# Voltage_Regulators.net
KiCad netlist of a schematic drawn in Altium Designer
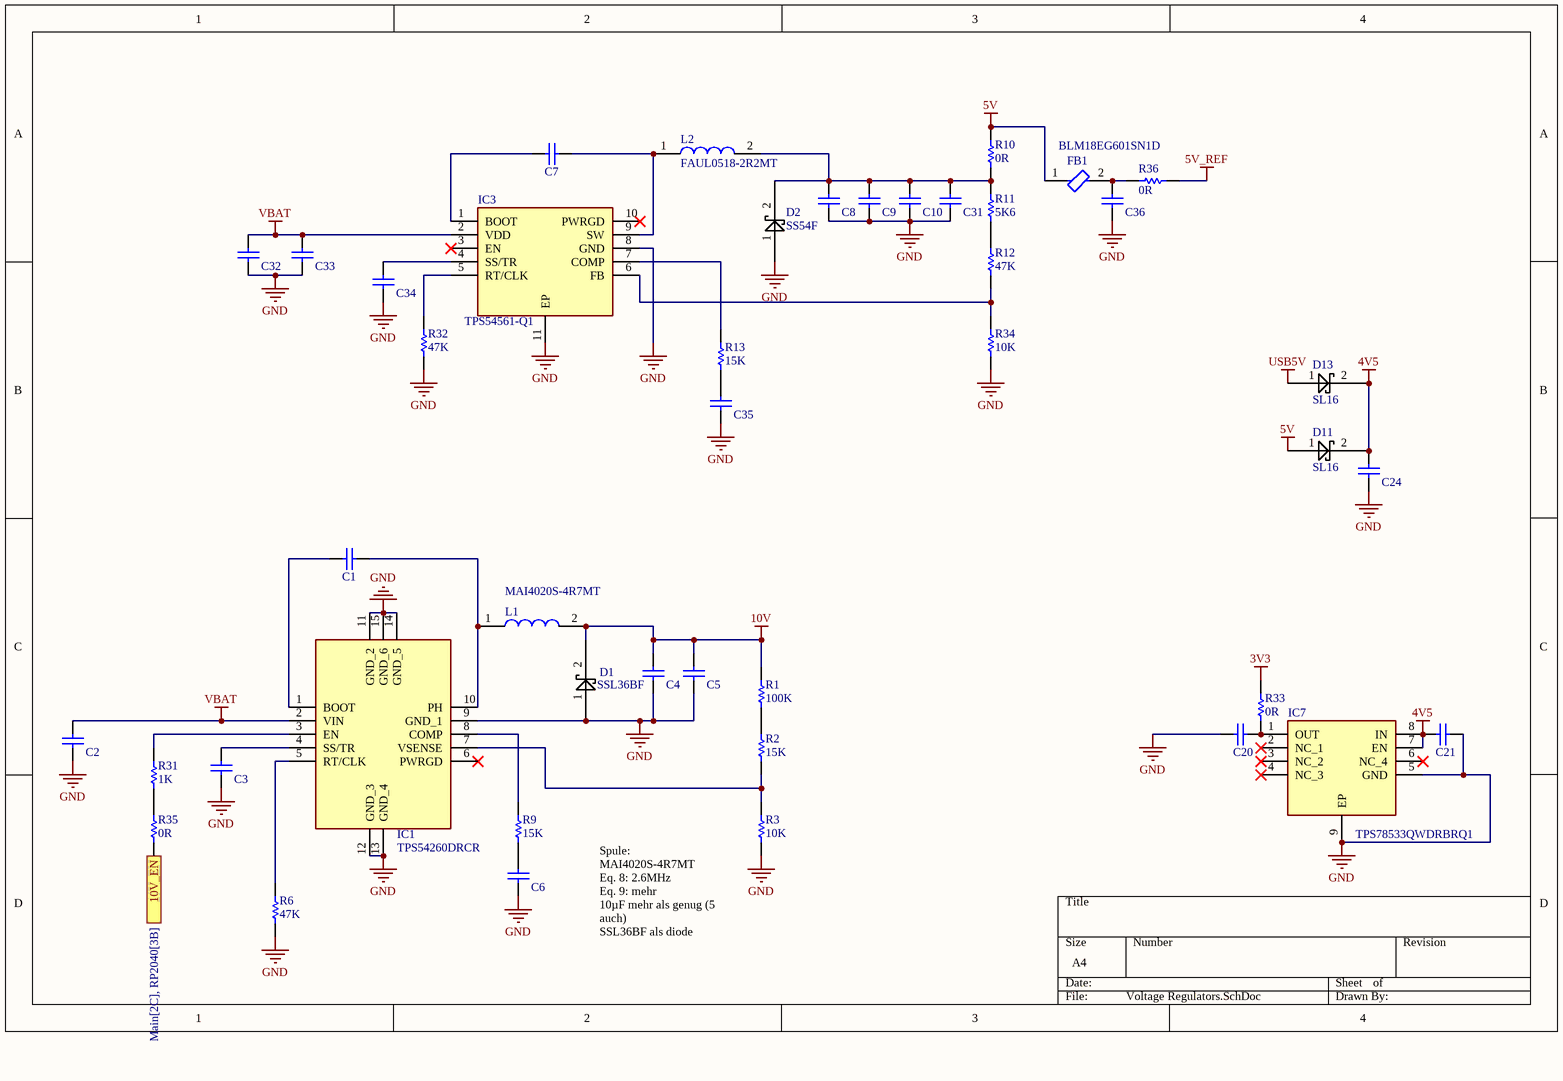
[diagram p0: Voltage Regulators.SchDoc]

(export (version "E")
  (design (tool "Eeschema 10.0.6"))
  (components
    (comp (ref "C1")
      (value "100nF")
      (footprint "WCAP-CSGP_0603_L1.6W0.8H0.8_Reflow")
      (description "WCAP-CSGP Multilayer Ceramic Chip Capacitor, General Purpose, size 0603, X7R, 100nF, 16VDC")
      (fields
        (field (name "MANUFACTURER PART NUMBER") "885012206046")
        (field (name "MANUFACTURER") "Wurth Elektronik")
      )
      (libsource (lib "Altium_WCAP-CSGP (rev22e)") (part "885012206046"))
    )
    (comp (ref "C2")
      (value "3.3µF")
      (footprint "WCAP-CSGP_1206_L3.2W1.6H1.6")
      (description "TDK C3216X7S2A335KT000N\r\n3.3µF MLCC 1206 100V X7S")
      (fields
        (field (name "MANUFACTURER PART NUMBER") "885012208124")
        (field (name "MANUFACTURER") "Wurth Elektronik")
      )
      (libsource (lib "Altium_WCAP-CSGP (rev22e)") (part "885012208124"))
    )
    (comp (ref "C3")
      (value "10nF")
      (footprint "WCAP-CSGP_0603_L1.6W0.8H0.8_Reflow")
      (description "WCAP-CSGP Multilayer Ceramic Chip Capacitor, General Purpose, size 0603, X7R, 10nF, 16VDC")
      (fields
        (field (name "MANUFACTURER PART NUMBER") "885012206040")
        (field (name "MANUFACTURER") "Wurth Elektronik")
      )
      (libsource (lib "Altium_WCAP-CSGP (rev22e)") (part "885012206040"))
    )
    (comp (ref "C4")
      (value "4.7µF")
      (footprint "WCAP-CSGP_0805_L2W1.25H1.25")
      (description "CL21A475KAQNNNG")
      (fields
        (field (name "MANUFACTURER PART NUMBER") "885012107013")
        (field (name "MANUFACTURER") "Wurth Elektronik")
      )
      (libsource (lib "Altium_WCAP-CSGP (rev22e)") (part "885012107013"))
    )
    (comp (ref "C5")
      (value "4.7µF")
      (footprint "WCAP-CSGP_0805_L2W1.25H1.25")
      (description "CL21A475KAQNNNG")
      (fields
        (field (name "MANUFACTURER PART NUMBER") "885012107013")
        (field (name "MANUFACTURER") "Wurth Elektronik")
      )
      (libsource (lib "Altium_WCAP-CSGP (rev22e)") (part "885012107013"))
    )
    (comp (ref "C6")
      (value "2.5pF")
      (footprint "WCAP-CSGP_0603_L1.6W0.8H0.8_Reflow")
      (description "TCC0603COG2R5C500CT")
      (fields
        (field (name "MANUFACTURER PART NUMBER") "885012006030")
        (field (name "MANUFACTURER") "Wurth Elektronik")
      )
      (libsource (lib "Altium_WCAP-CSGP (rev22e)") (part "885012006030"))
    )
    (comp (ref "C7")
      (value "100nF")
      (footprint "WCAP-CSGP_0603_L1.6W0.8H0.8_Reflow")
      (description "WCAP-CSGP Multilayer Ceramic Chip Capacitor, General Purpose, size 0603, X7R, 100nF, 16VDC")
      (fields
        (field (name "MANUFACTURER PART NUMBER") "885012206046")
        (field (name "MANUFACTURER") "Wurth Elektronik")
      )
      (libsource (lib "Altium_WCAP-CSGP (rev22e)") (part "885012206046"))
    )
    (comp (ref "C8")
      (value "4.7µF")
      (footprint "WCAP-CSGP_0805_L2W1.25H1.25")
      (description "CL21A475KAQNNNG")
      (fields
        (field (name "MANUFACTURER PART NUMBER") "885012107013")
        (field (name "MANUFACTURER") "Wurth Elektronik")
      )
      (libsource (lib "Altium_WCAP-CSGP (rev22e)") (part "885012107013"))
    )
    (comp (ref "C9")
      (value "4.7µF")
      (footprint "WCAP-CSGP_0805_L2W1.25H1.25")
      (description "CL21A475KAQNNNG")
      (fields
        (field (name "MANUFACTURER PART NUMBER") "885012107013")
        (field (name "MANUFACTURER") "Wurth Elektronik")
      )
      (libsource (lib "Altium_WCAP-CSGP (rev22e)") (part "885012107013"))
    )
    (comp (ref "C10")
      (value "4.7µF")
      (footprint "WCAP-CSGP_0805_L2W1.25H1.25")
      (description "CL21A475KAQNNNG")
      (fields
        (field (name "MANUFACTURER PART NUMBER") "885012107013")
        (field (name "MANUFACTURER") "Wurth Elektronik")
      )
      (libsource (lib "Altium_WCAP-CSGP (rev22e)") (part "885012107013"))
    )
    (comp (ref "C20")
      (value "1µF")
      (footprint "WCAP-CSGP_0603_L1.6W0.8H0.8_Reflow")
      (description "WCAP-CSGP Multilayer Ceramic Chip Capacitor, General Purpose, size 0603, X7R, 1µF, 10VDC")
      (fields
        (field (name "MANUFACTURER PART NUMBER") "885012206026")
        (field (name "MANUFACTURER") "Wurth Elektronik")
      )
      (libsource (lib "Altium_WCAP-CSGP (rev22e)") (part "885012206026"))
    )
    (comp (ref "C21")
      (value "1µF")
      (footprint "WCAP-CSGP_0603_L1.6W0.8H0.8_Reflow")
      (description "WCAP-CSGP Multilayer Ceramic Chip Capacitor, General Purpose, size 0603, X7R, 1µF, 10VDC")
      (fields
        (field (name "MANUFACTURER PART NUMBER") "885012206026")
        (field (name "MANUFACTURER") "Wurth Elektronik")
      )
      (libsource (lib "Altium_WCAP-CSGP (rev22e)") (part "885012206026"))
    )
    (comp (ref "C24")
      (value "1µF")
      (footprint "WCAP-CSGP_0603_L1.6W0.8H0.8_Reflow")
      (description "WCAP-CSGP Multilayer Ceramic Chip Capacitor, General Purpose, size 0603, X5R, 1µF, 16VDC")
      (fields
        (field (name "MANUFACTURER PART NUMBER") "885012106017")
        (field (name "MANUFACTURER") "Wurth Elektronik")
      )
      (libsource (lib "Altium_WCAP-CSGP (rev22e)") (part "885012106017"))
    )
    (comp (ref "C31")
      (value "4.7µF")
      (footprint "WCAP-CSGP_0805_L2W1.25H1.25")
      (description "CL21A475KAQNNNG")
      (fields
        (field (name "MANUFACTURER PART NUMBER") "885012107013")
        (field (name "MANUFACTURER") "Wurth Elektronik")
      )
      (libsource (lib "Altium_WCAP-CSGP (rev22e)") (part "885012107013"))
    )
    (comp (ref "C32")
      (value "2.2µF")
      (footprint "WCAP-CSGP_0805_L2W1.25H1.25")
      (description "CL21B225KBYNNNE")
      (fields
        (field (name "MANUFACTURER PART NUMBER") "885012107013")
        (field (name "MANUFACTURER") "Wurth Elektronik")
      )
      (libsource (lib "Altium_WCAP-CSGP (rev22e)") (part "885012107013"))
    )
    (comp (ref "C33")
      (value "2.2µF")
      (footprint "WCAP-CSGP_0805_L2W1.25H1.25")
      (description "CL21B225KBYNNNE")
      (fields
        (field (name "MANUFACTURER PART NUMBER") "885012107013")
        (field (name "MANUFACTURER") "Wurth Elektronik")
      )
      (libsource (lib "Altium_WCAP-CSGP (rev22e)") (part "885012107013"))
    )
    (comp (ref "C34")
      (value "10nF")
      (footprint "WCAP-CSGP_0603_L1.6W0.8H0.8_Reflow")
      (description "WCAP-CSGP Multilayer Ceramic Chip Capacitor, General Purpose, size 0603, X7R, 10nF, 16VDC")
      (fields
        (field (name "MANUFACTURER PART NUMBER") "885012206040")
        (field (name "MANUFACTURER") "Wurth Elektronik")
      )
      (libsource (lib "Altium_WCAP-CSGP (rev22e)") (part "885012206040"))
    )
    (comp (ref "C35")
      (value "1nF")
      (footprint "WCAP-CSGP_0603_L1.6W0.8H0.8_Reflow")
      (description "TCC0603COG2R5C500CT")
      (fields
        (field (name "MANUFACTURER PART NUMBER") "885012006030")
        (field (name "MANUFACTURER") "Wurth Elektronik")
      )
      (libsource (lib "Altium_WCAP-CSGP (rev22e)") (part "885012006030"))
    )
    (comp (ref "C36")
      (value "1µF")
      (footprint "WCAP-CSGP_0603_L1.6W0.8H0.8_Reflow")
      (description "WCAP-CSGP Multilayer Ceramic Chip Capacitor, General Purpose, size 0603, X7R, 1µF, 10VDC")
      (fields
        (field (name "MANUFACTURER PART NUMBER") "885012206026")
        (field (name "MANUFACTURER") "Wurth Elektronik")
      )
      (libsource (lib "Altium_WCAP-CSGP (rev22e)") (part "885012206026"))
    )
    (comp (ref "D1")
      (value "SSL36BF")
      (footprint "SSL36BF")
      (libsource (lib "Custom Components") (part "SSL36BF"))
    )
    (comp (ref "D2") (value "SS54F") (footprint "SS54F") (libsource (lib "Custom Components") (part "SS54F")))
    (comp (ref "D11") (value "SL16") (footprint "SL16") (libsource (lib "Custom Components") (part "SL16")))
    (comp (ref "D13") (value "SL16") (footprint "SL16") (libsource (lib "Custom Components") (part "SL16")))
    (comp (ref "FB1")
      (value "BLM18EG601SN1D")
      (footprint "FP-BLM18-0_15-t0_8-MFG")
      (description "Chip Ferrite Bead, 0603, 600Ω @ 100MHz, 0.35Ω, 25%, 500mA")
      (fields (field (name "TOLERANCE") "25%"))
      (libsource (lib "Altium Content Vault") (part "5f30dd21d616792df468990f7003faa"))
    )
    (comp (ref "IC1")
      (value "TPS54260DRCR")
      (footprint "Custom Components:TPS54040ADRCT")
      (description "Integrated Circuit")
      (fields (field (name "MOUSER PART NUMBER") "595-TPS54260DRCR"))
      (libsource (lib "*") (part "TPS54260DRCR"))
    )
    (comp (ref "IC3")
      (value "TPS54561-Q1")
      (footprint "Custom Components:SON80P400X400X80-11N")
      (description "Integrated Circuit")
      (libsource (lib "*") (part "TPS54561-Q1"))
    )
    (comp (ref "IC7")
      (value "TPS78533QWDRBRQ1")
      (footprint "Custom Components:SON65P300X300X100-9N-D")
      (description "Integrated Circuit")
      (fields (field (name "MOUSER PART NUMBER") "595-TPS78533QWDRBRQ1"))
      (libsource (lib "*") (part "TPS78533QWDRBRQ1"))
    )
    (comp (ref "L1")
      (value "MAI4020S-4R7MT")
      (footprint "MAI4020S-4R7MT")
      (libsource (lib "Custom Components") (part "MAI4020S-4R7MT"))
    )
    (comp (ref "L2")
      (value "FAUL0518-2R2MT")
      (footprint "FAUL0518-2R2MT")
      (libsource (lib "Custom Components") (part "FAUL0518-2R2MT"))
    )
    (comp (ref "R1")
      (value "100K")
      (footprint "RESC0603(1608)_N")
      (description "Chipwiderstand, SMD, Baureihe MC, 1%")
      (fields (field (name "MANUFACTURER") "Multicomp"))
      (libsource (lib "Standardbauteile") (part "Res 100K"))
    )
    (comp (ref "R2")
      (value "15K")
      (footprint "RESC0603(1608)_N")
      (description "Chipwiderstand, SMD, Baureihe MC, 1%")
      (fields (field (name "MANUFACTURER") "Multicomp"))
      (libsource (lib "Standardbauteile") (part "Res 12K"))
    )
    (comp (ref "R3")
      (value "10K")
      (footprint "RESC0603(1608)_N")
      (description "Chipwiderstand, SMD, Baureihe MC, 1%")
      (fields (field (name "MANUFACTURER") "Multicomp"))
      (libsource (lib "Standardbauteile") (part "Res 10K"))
    )
    (comp (ref "R6")
      (value "47K")
      (footprint "RESC0603(1608)_N")
      (description "Chipwiderstand, SMD, Baureihe MC, 1%")
      (fields (field (name "MANUFACTURER") "Multicomp"))
      (libsource (lib "Standardbauteile") (part "Res 47R"))
    )
    (comp (ref "R9")
      (value "15K")
      (footprint "RESC0603(1608)_N")
      (description "Chipwiderstand, SMD, Baureihe MC, 1%")
      (fields (field (name "MANUFACTURER") "Multicomp"))
      (libsource (lib "Standardbauteile") (part "Res 12K"))
    )
    (comp (ref "R10")
      (value "0R")
      (footprint "RESC0603(1608)_N")
      (description "Chipwiderstand, SMD, Baureihe MC, 1%")
      (fields (field (name "MANUFACTURER") "Multicomp"))
      (libsource (lib "Standardbauteile") (part "Res 0R"))
    )
    (comp (ref "R11")
      (value "5K6")
      (footprint "RESC0603(1608)_N")
      (description "Chipwiderstand, SMD, Baureihe MC, 1%")
      (fields (field (name "MANUFACTURER") "Multicomp"))
      (libsource (lib "Standardbauteile") (part "Res 100K"))
    )
    (comp (ref "R12")
      (value "47K")
      (footprint "RESC0603(1608)_N")
      (description "Chipwiderstand, SMD, Baureihe MC, 1%")
      (fields (field (name "MANUFACTURER") "Multicomp"))
      (libsource (lib "Standardbauteile") (part "Res 12K"))
    )
    (comp (ref "R13")
      (value "15K")
      (footprint "RESC0603(1608)_N")
      (description "Chipwiderstand, SMD, Baureihe MC, 1%")
      (fields (field (name "MANUFACTURER") "Multicomp"))
      (libsource (lib "Standardbauteile") (part "Res 12K"))
    )
    (comp (ref "R31")
      (value "1K")
      (footprint "RESC0603(1608)_N")
      (description "Chipwiderstand, SMD, Baureihe MC, 1%")
      (fields (field (name "MANUFACTURER") "Multicomp"))
      (libsource (lib "Standardbauteile") (part "Res 1K"))
    )
    (comp (ref "R32")
      (value "47K")
      (footprint "RESC0603(1608)_N")
      (description "Chipwiderstand, SMD, Baureihe MC, 1%")
      (fields (field (name "MANUFACTURER") "Multicomp"))
      (libsource (lib "Standardbauteile") (part "Res 47R"))
    )
    (comp (ref "R33")
      (value "0R")
      (footprint "RESC0603(1608)_N")
      (description "Chipwiderstand, SMD, Baureihe MC, 1%")
      (fields (field (name "MANUFACTURER") "Multicomp"))
      (libsource (lib "Standardbauteile") (part "Res 0R"))
    )
    (comp (ref "R34")
      (value "10K")
      (footprint "RESC0603(1608)_N")
      (description "Chipwiderstand, SMD, Baureihe MC, 1%")
      (fields (field (name "MANUFACTURER") "Multicomp"))
      (libsource (lib "Standardbauteile") (part "Res 10K"))
    )
    (comp (ref "R35")
      (value "0R")
      (footprint "RESC0603(1608)_N")
      (description "Chipwiderstand, SMD, Baureihe MC, 1%")
      (fields (field (name "MANUFACTURER") "Multicomp"))
      (libsource (lib "Standardbauteile") (part "Res 0R"))
    )
    (comp (ref "R36")
      (value "0R")
      (footprint "RESC0603(1608)_N")
      (description "Chipwiderstand, SMD, Baureihe MC, 1%")
      (fields (field (name "MANUFACTURER") "Multicomp"))
      (libsource (lib "Standardbauteile") (part "Res 0R"))
    )
  )
  (nets
    (net (code "1") (name "/10V_EN") (class "Default")
      (node (ref "R35") (pin "1") (pinfunction "1_1") (pintype "passive"))
    )
    (net (code "2") (name "3V3") (class "Default")
      (node (ref "R33") (pin "2") (pinfunction "2_2") (pintype "passive"))
    )
    (net (code "3") (name "4V5") (class "Default")
      (node (ref "C21") (pin "1") (pinfunction "1_1") (pintype "passive"))
      (node (ref "C24") (pin "2") (pinfunction "2_2") (pintype "passive"))
      (node (ref "D11") (pin "2") (pinfunction "6_2") (pintype "passive"))
      (node (ref "D13") (pin "2") (pinfunction "6_2") (pintype "passive"))
      (node (ref "IC7") (pin "7") (pinfunction "EN_7") (pintype "passive"))
      (node (ref "IC7") (pin "8") (pinfunction "IN_8") (pintype "passive"))
    )
    (net (code "4") (name "5V") (class "Default")
      (node (ref "D11") (pin "1") (pinfunction "5_1") (pintype "passive"))
      (node (ref "FB1") (pin "1") (pinfunction "1_1") (pintype "passive"))
      (node (ref "R10") (pin "2") (pinfunction "2_2") (pintype "passive"))
    )
    (net (code "5") (name "5V_REF") (class "Default")
      (node (ref "R36") (pin "2") (pinfunction "2_2") (pintype "passive"))
    )
    (net (code "6") (name "10V") (class "Default")
      (node (ref "C4") (pin "2") (pinfunction "2_2") (pintype "passive"))
      (node (ref "C5") (pin "2") (pinfunction "2_2") (pintype "passive"))
      (node (ref "D1") (pin "2") (pinfunction "6_2") (pintype "passive"))
      (node (ref "L1") (pin "2") (pinfunction "2_2") (pintype "passive"))
      (node (ref "R1") (pin "2") (pinfunction "2_2") (pintype "passive"))
    )
    (net (code "7") (name "GND") (class "Default")
      (node (ref "C10") (pin "1") (pinfunction "1_1") (pintype "passive"))
      (node (ref "C2") (pin "1") (pinfunction "1_1") (pintype "passive"))
      (node (ref "C20") (pin "1") (pinfunction "1_1") (pintype "passive"))
      (node (ref "C21") (pin "2") (pinfunction "2_2") (pintype "passive"))
      (node (ref "C24") (pin "1") (pinfunction "1_1") (pintype "passive"))
      (node (ref "C3") (pin "1") (pinfunction "1_1") (pintype "passive"))
      (node (ref "C31") (pin "1") (pinfunction "1_1") (pintype "passive"))
      (node (ref "C32") (pin "1") (pinfunction "1_1") (pintype "passive"))
      (node (ref "C33") (pin "1") (pinfunction "1_1") (pintype "passive"))
      (node (ref "C34") (pin "1") (pinfunction "1_1") (pintype "passive"))
      (node (ref "C35") (pin "1") (pinfunction "1_1") (pintype "passive"))
      (node (ref "C36") (pin "1") (pinfunction "1_1") (pintype "passive"))
      (node (ref "C4") (pin "1") (pinfunction "1_1") (pintype "passive"))
      (node (ref "C5") (pin "1") (pinfunction "1_1") (pintype "passive"))
      (node (ref "C6") (pin "1") (pinfunction "1_1") (pintype "passive"))
      (node (ref "C8") (pin "1") (pinfunction "1_1") (pintype "passive"))
      (node (ref "C9") (pin "1") (pinfunction "1_1") (pintype "passive"))
      (node (ref "D1") (pin "1") (pinfunction "5_1") (pintype "passive"))
      (node (ref "D2") (pin "1") (pinfunction "5_1") (pintype "passive"))
      (node (ref "IC1") (pin "11") (pinfunction "GND_2_11") (pintype "passive"))
      (node (ref "IC1") (pin "12") (pinfunction "GND_3_12") (pintype "passive"))
      (node (ref "IC1") (pin "13") (pinfunction "GND_4_13") (pintype "passive"))
      (node (ref "IC1") (pin "14") (pinfunction "GND_5_14") (pintype "passive"))
      (node (ref "IC1") (pin "15") (pinfunction "GND_6_15") (pintype "passive"))
      (node (ref "IC1") (pin "9") (pinfunction "GND_1_9") (pintype "passive"))
      (node (ref "IC3") (pin "11") (pinfunction "EP_11") (pintype "passive"))
      (node (ref "IC3") (pin "8") (pinfunction "GND_8") (pintype "passive"))
      (node (ref "IC7") (pin "5") (pinfunction "GND_5") (pintype "passive"))
      (node (ref "IC7") (pin "9") (pinfunction "EP_9") (pintype "passive"))
      (node (ref "R3") (pin "1") (pinfunction "1_1") (pintype "passive"))
      (node (ref "R32") (pin "1") (pinfunction "1_1") (pintype "passive"))
      (node (ref "R34") (pin "1") (pinfunction "1_1") (pintype "passive"))
      (node (ref "R6") (pin "1") (pinfunction "1_1") (pintype "passive"))
    )
    (net (code "8") (name "Net-(C6-Pad2)") (class "Default")
      (node (ref "C6") (pin "2") (pinfunction "2_2") (pintype "passive"))
      (node (ref "R9") (pin "1") (pinfunction "1_1") (pintype "passive"))
    )
    (net (code "9") (name "Net-(C35-Pad2)") (class "Default")
      (node (ref "C35") (pin "2") (pinfunction "2_2") (pintype "passive"))
      (node (ref "R13") (pin "1") (pinfunction "1_1") (pintype "passive"))
    )
    (net (code "10") (name "Net-(C36-Pad2)") (class "Default")
      (node (ref "C36") (pin "2") (pinfunction "2_2") (pintype "passive"))
      (node (ref "FB1") (pin "2") (pinfunction "2_2") (pintype "passive"))
      (node (ref "R36") (pin "1") (pinfunction "1_1") (pintype "passive"))
    )
    (net (code "11") (name "Net-(D2-6)") (class "Default")
      (node (ref "C10") (pin "2") (pinfunction "2_2") (pintype "passive"))
      (node (ref "C31") (pin "2") (pinfunction "2_2") (pintype "passive"))
      (node (ref "C8") (pin "2") (pinfunction "2_2") (pintype "passive"))
      (node (ref "C9") (pin "2") (pinfunction "2_2") (pintype "passive"))
      (node (ref "D2") (pin "2") (pinfunction "6_2") (pintype "passive"))
      (node (ref "L2") (pin "2") (pinfunction "2_2") (pintype "passive"))
      (node (ref "R10") (pin "1") (pinfunction "1_1") (pintype "passive"))
      (node (ref "R11") (pin "2") (pinfunction "2_2") (pintype "passive"))
    )
    (net (code "12") (name "Net-(IC1-BOOT)") (class "Default")
      (node (ref "C1") (pin "1") (pinfunction "1_1") (pintype "passive"))
      (node (ref "IC1") (pin "1") (pinfunction "BOOT_1") (pintype "passive"))
    )
    (net (code "13") (name "Net-(IC1-COMP)") (class "Default")
      (node (ref "IC1") (pin "8") (pinfunction "COMP_8") (pintype "passive"))
      (node (ref "R9") (pin "2") (pinfunction "2_2") (pintype "passive"))
    )
    (net (code "14") (name "Net-(IC1-EN)") (class "Default")
      (node (ref "IC1") (pin "3") (pinfunction "EN_3") (pintype "passive"))
      (node (ref "R31") (pin "2") (pinfunction "2_2") (pintype "passive"))
    )
    (net (code "15") (name "Net-(IC1-PH)") (class "Default")
      (node (ref "C1") (pin "2") (pinfunction "2_2") (pintype "passive"))
      (node (ref "IC1") (pin "10") (pinfunction "PH_10") (pintype "passive"))
      (node (ref "L1") (pin "1") (pinfunction "1_1") (pintype "passive"))
    )
    (net (code "16") (name "Net-(IC1-RT{slash}CLK)") (class "Default")
      (node (ref "IC1") (pin "5") (pinfunction "RT/CLK_5") (pintype "passive"))
      (node (ref "R6") (pin "2") (pinfunction "2_2") (pintype "passive"))
    )
    (net (code "17") (name "Net-(IC1-SS{slash}TR)") (class "Default")
      (node (ref "C3") (pin "2") (pinfunction "2_2") (pintype "passive"))
      (node (ref "IC1") (pin "4") (pinfunction "SS/TR_4") (pintype "passive"))
    )
    (net (code "18") (name "Net-(IC1-VSENSE)") (class "Default")
      (node (ref "IC1") (pin "7") (pinfunction "VSENSE_7") (pintype "passive"))
      (node (ref "R2") (pin "1") (pinfunction "1_1") (pintype "passive"))
      (node (ref "R3") (pin "2") (pinfunction "2_2") (pintype "passive"))
    )
    (net (code "19") (name "Net-(IC3-BOOT)") (class "Default")
      (node (ref "C7") (pin "1") (pinfunction "1_1") (pintype "passive"))
      (node (ref "IC3") (pin "1") (pinfunction "BOOT_1") (pintype "passive"))
    )
    (net (code "20") (name "Net-(IC3-COMP)") (class "Default")
      (node (ref "IC3") (pin "7") (pinfunction "COMP_7") (pintype "passive"))
      (node (ref "R13") (pin "2") (pinfunction "2_2") (pintype "passive"))
    )
    (net (code "21") (name "Net-(IC3-FB)") (class "Default")
      (node (ref "IC3") (pin "6") (pinfunction "FB_6") (pintype "passive"))
      (node (ref "R12") (pin "1") (pinfunction "1_1") (pintype "passive"))
      (node (ref "R34") (pin "2") (pinfunction "2_2") (pintype "passive"))
    )
    (net (code "22") (name "Net-(IC3-RT{slash}CLK)") (class "Default")
      (node (ref "IC3") (pin "5") (pinfunction "RT/CLK_5") (pintype "passive"))
      (node (ref "R32") (pin "2") (pinfunction "2_2") (pintype "passive"))
    )
    (net (code "23") (name "Net-(IC3-SS{slash}TR)") (class "Default")
      (node (ref "C34") (pin "2") (pinfunction "2_2") (pintype "passive"))
      (node (ref "IC3") (pin "4") (pinfunction "SS/TR_4") (pintype "passive"))
    )
    (net (code "24") (name "Net-(IC3-SW)") (class "Default")
      (node (ref "C7") (pin "2") (pinfunction "2_2") (pintype "passive"))
      (node (ref "IC3") (pin "9") (pinfunction "SW_9") (pintype "passive"))
      (node (ref "L2") (pin "1") (pinfunction "1_1") (pintype "passive"))
    )
    (net (code "25") (name "Net-(IC7-OUT)") (class "Default")
      (node (ref "C20") (pin "2") (pinfunction "2_2") (pintype "passive"))
      (node (ref "IC7") (pin "1") (pinfunction "OUT_1") (pintype "passive"))
      (node (ref "R33") (pin "1") (pinfunction "1_1") (pintype "passive"))
    )
    (net (code "26") (name "Net-(R1-Pad1)") (class "Default")
      (node (ref "R1") (pin "1") (pinfunction "1_1") (pintype "passive"))
      (node (ref "R2") (pin "2") (pinfunction "2_2") (pintype "passive"))
    )
    (net (code "27") (name "Net-(R11-Pad1)") (class "Default")
      (node (ref "R11") (pin "1") (pinfunction "1_1") (pintype "passive"))
      (node (ref "R12") (pin "2") (pinfunction "2_2") (pintype "passive"))
    )
    (net (code "28") (name "Net-(R31-Pad1)") (class "Default")
      (node (ref "R31") (pin "1") (pinfunction "1_1") (pintype "passive"))
      (node (ref "R35") (pin "2") (pinfunction "2_2") (pintype "passive"))
    )
    (net (code "29") (name "USB5V") (class "Default")
      (node (ref "D13") (pin "1") (pinfunction "5_1") (pintype "passive"))
    )
    (net (code "30") (name "VBAT") (class "Default")
      (node (ref "C2") (pin "2") (pinfunction "2_2") (pintype "passive"))
      (node (ref "C32") (pin "2") (pinfunction "2_2") (pintype "passive"))
      (node (ref "C33") (pin "2") (pinfunction "2_2") (pintype "passive"))
      (node (ref "IC1") (pin "2") (pinfunction "VIN_2") (pintype "passive"))
      (node (ref "IC3") (pin "2") (pinfunction "VDD_2") (pintype "passive"))
    )
    (net (code "31") (name "unconnected-(IC1-PWRGD-Pad6)") (class "Default")
      (node (ref "IC1") (pin "6") (pinfunction "PWRGD_6") (pintype "passive+no_connect"))
    )
    (net (code "32") (name "unconnected-(IC3-EN-Pad3)") (class "Default")
      (node (ref "IC3") (pin "3") (pinfunction "EN_3") (pintype "passive+no_connect"))
    )
    (net (code "33") (name "unconnected-(IC3-PWRGD-Pad10)") (class "Default")
      (node (ref "IC3") (pin "10") (pinfunction "PWRGD_10") (pintype "passive+no_connect"))
    )
    (net (code "34") (name "unconnected-(IC7-NC_1-Pad2)") (class "Default")
      (node (ref "IC7") (pin "2") (pinfunction "NC_1_2") (pintype "passive+no_connect"))
    )
    (net (code "35") (name "unconnected-(IC7-NC_2-Pad3)") (class "Default")
      (node (ref "IC7") (pin "3") (pinfunction "NC_2_3") (pintype "passive+no_connect"))
    )
    (net (code "36") (name "unconnected-(IC7-NC_3-Pad4)") (class "Default")
      (node (ref "IC7") (pin "4") (pinfunction "NC_3_4") (pintype "passive+no_connect"))
    )
    (net (code "37") (name "unconnected-(IC7-NC_4-Pad6)") (class "Default")
      (node (ref "IC7") (pin "6") (pinfunction "NC_4_6") (pintype "passive+no_connect"))
    )
  )
)
